# spider.net
KiCad netlist of a schematic drawn in EAGLE
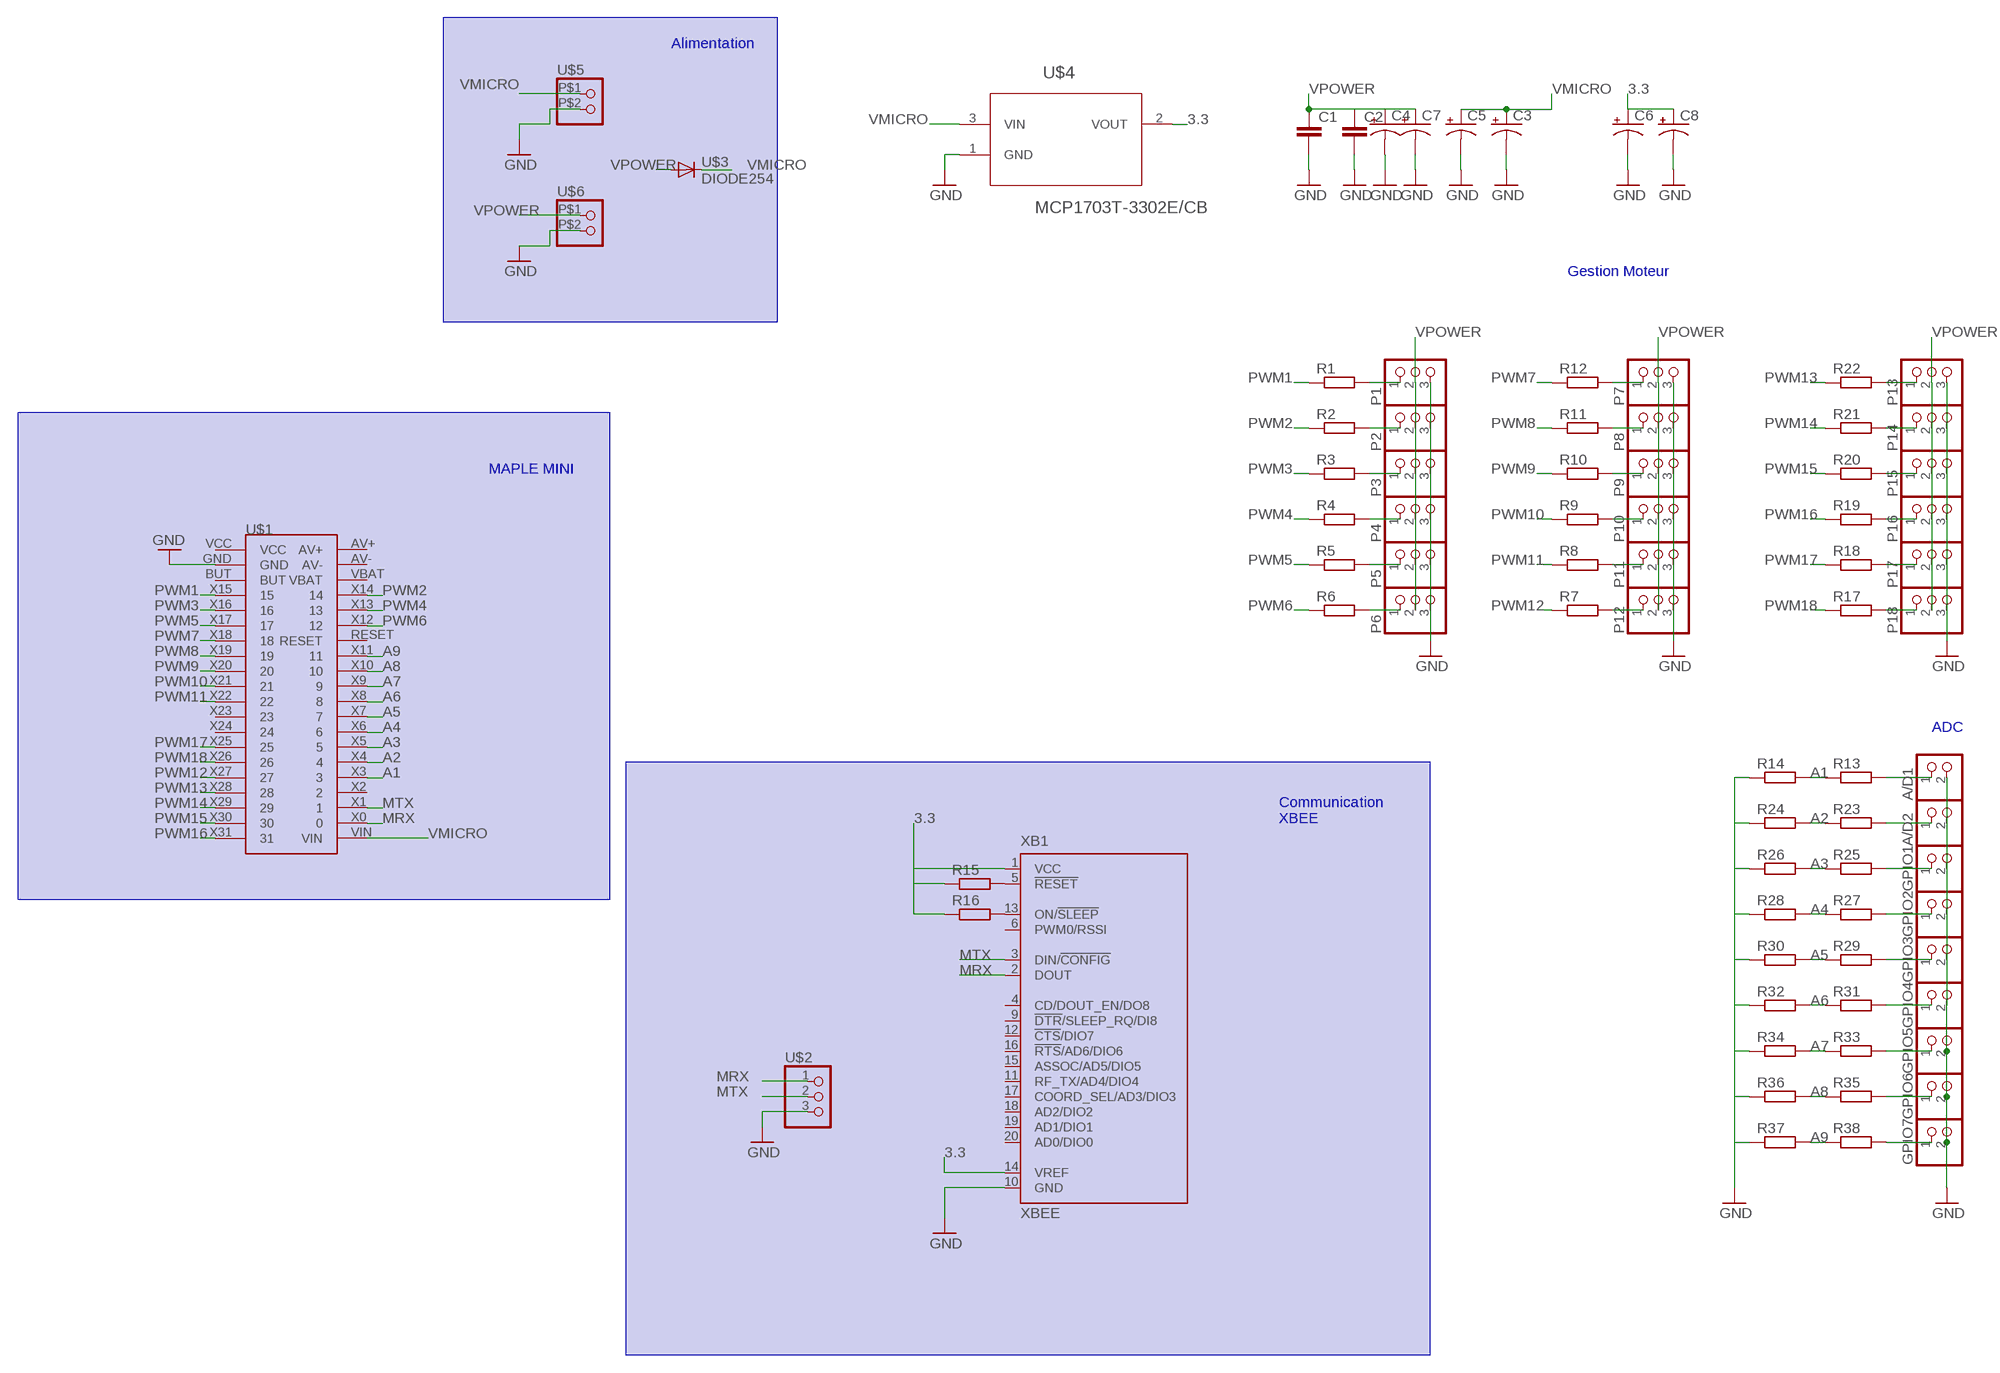
[diagram p0: schematic, sheet 1]

(export (version "E")
  (design (tool "Eeschema 10.0.6"))
  (components
    (comp (ref "A/D1")
      (value "CONNEC_1X02")
      (footprint "eagle-import:CONNEC_1X02")
      (libsource (lib "eagle-import") (part "rhoban_CONNEC_1X02"))
    )
    (comp (ref "A/D2")
      (value "CONNEC_1X02")
      (footprint "eagle-import:CONNEC_1X02")
      (libsource (lib "eagle-import") (part "rhoban_CONNEC_1X02"))
    )
    (comp (ref "C1")
      (value "C-EU075-032X103")
      (footprint "eagle-import:C075-032X103")
      (libsource (lib "eagle-import") (part "C-EU075-032X103"))
    )
    (comp (ref "C2")
      (value "C-EU075-032X103")
      (footprint "eagle-import:C075-032X103")
      (libsource (lib "eagle-import") (part "C-EU075-032X103"))
    )
    (comp (ref "C3")
      (value "CAP_POLPTH2")
      (footprint "eagle-import:CPOL-RADIAL-10UF-25V")
      (libsource (lib "eagle-import") (part "CAP_POLPTH2"))
    )
    (comp (ref "C4")
      (value "CAP_POLPTH2")
      (footprint "eagle-import:CPOL-RADIAL-10UF-25V")
      (libsource (lib "eagle-import") (part "CAP_POLPTH2"))
    )
    (comp (ref "C5")
      (value "CAP_POLPTH2")
      (footprint "eagle-import:CPOL-RADIAL-10UF-25V")
      (libsource (lib "eagle-import") (part "CAP_POLPTH2"))
    )
    (comp (ref "C6")
      (value "CAP_POLPTH2")
      (footprint "eagle-import:CPOL-RADIAL-10UF-25V")
      (libsource (lib "eagle-import") (part "CAP_POLPTH2"))
    )
    (comp (ref "C7")
      (value "CAP_POLPTH2")
      (footprint "eagle-import:CPOL-RADIAL-10UF-25V")
      (libsource (lib "eagle-import") (part "CAP_POLPTH2"))
    )
    (comp (ref "C8")
      (value "CAP_POLPTH2")
      (footprint "eagle-import:CPOL-RADIAL-10UF-25V")
      (libsource (lib "eagle-import") (part "CAP_POLPTH2"))
    )
    (comp (ref "GPIO1")
      (value "CONNEC_1X02")
      (footprint "eagle-import:CONNEC_1X02")
      (libsource (lib "eagle-import") (part "rhoban_CONNEC_1X02"))
    )
    (comp (ref "GPIO2")
      (value "CONNEC_1X02")
      (footprint "eagle-import:CONNEC_1X02")
      (libsource (lib "eagle-import") (part "rhoban_CONNEC_1X02"))
    )
    (comp (ref "GPIO3")
      (value "CONNEC_1X02")
      (footprint "eagle-import:CONNEC_1X02")
      (libsource (lib "eagle-import") (part "rhoban_CONNEC_1X02"))
    )
    (comp (ref "GPIO4")
      (value "CONNEC_1X02")
      (footprint "eagle-import:CONNEC_1X02")
      (libsource (lib "eagle-import") (part "rhoban_CONNEC_1X02"))
    )
    (comp (ref "GPIO5")
      (value "CONNEC_1X02")
      (footprint "eagle-import:CONNEC_1X02")
      (libsource (lib "eagle-import") (part "rhoban_CONNEC_1X02"))
    )
    (comp (ref "GPIO6")
      (value "CONNEC_1X02")
      (footprint "eagle-import:CONNEC_1X02")
      (libsource (lib "eagle-import") (part "rhoban_CONNEC_1X02"))
    )
    (comp (ref "GPIO7")
      (value "CONNEC_1X02")
      (footprint "eagle-import:CONNEC_1X02")
      (libsource (lib "eagle-import") (part "rhoban_CONNEC_1X02"))
    )
    (comp (ref "P1")
      (value "CONNEC_1X03")
      (footprint "eagle-import:CONNEC_1X03")
      (libsource (lib "eagle-import") (part "rhoban_CONNEC_1X03"))
    )
    (comp (ref "P2")
      (value "CONNEC_1X03")
      (footprint "eagle-import:CONNEC_1X03")
      (libsource (lib "eagle-import") (part "rhoban_CONNEC_1X03"))
    )
    (comp (ref "P3")
      (value "CONNEC_1X03")
      (footprint "eagle-import:CONNEC_1X03")
      (libsource (lib "eagle-import") (part "rhoban_CONNEC_1X03"))
    )
    (comp (ref "P4")
      (value "CONNEC_1X03")
      (footprint "eagle-import:CONNEC_1X03")
      (libsource (lib "eagle-import") (part "rhoban_CONNEC_1X03"))
    )
    (comp (ref "P5")
      (value "CONNEC_1X03")
      (footprint "eagle-import:CONNEC_1X03")
      (libsource (lib "eagle-import") (part "rhoban_CONNEC_1X03"))
    )
    (comp (ref "P6")
      (value "CONNEC_1X03")
      (footprint "eagle-import:CONNEC_1X03")
      (libsource (lib "eagle-import") (part "rhoban_CONNEC_1X03"))
    )
    (comp (ref "P7")
      (value "CONNEC_1X03")
      (footprint "eagle-import:CONNEC_1X03")
      (libsource (lib "eagle-import") (part "rhoban_CONNEC_1X03"))
    )
    (comp (ref "P8")
      (value "CONNEC_1X03")
      (footprint "eagle-import:CONNEC_1X03")
      (libsource (lib "eagle-import") (part "rhoban_CONNEC_1X03"))
    )
    (comp (ref "P9")
      (value "CONNEC_1X03")
      (footprint "eagle-import:CONNEC_1X03")
      (libsource (lib "eagle-import") (part "rhoban_CONNEC_1X03"))
    )
    (comp (ref "P10")
      (value "CONNEC_1X03")
      (footprint "eagle-import:CONNEC_1X03")
      (libsource (lib "eagle-import") (part "rhoban_CONNEC_1X03"))
    )
    (comp (ref "P11")
      (value "CONNEC_1X03")
      (footprint "eagle-import:CONNEC_1X03")
      (libsource (lib "eagle-import") (part "rhoban_CONNEC_1X03"))
    )
    (comp (ref "P12")
      (value "CONNEC_1X03")
      (footprint "eagle-import:CONNEC_1X03")
      (libsource (lib "eagle-import") (part "rhoban_CONNEC_1X03"))
    )
    (comp (ref "P13")
      (value "CONNEC_1X03")
      (footprint "eagle-import:CONNEC_1X03")
      (libsource (lib "eagle-import") (part "rhoban_CONNEC_1X03"))
    )
    (comp (ref "P14")
      (value "CONNEC_1X03")
      (footprint "eagle-import:CONNEC_1X03")
      (libsource (lib "eagle-import") (part "rhoban_CONNEC_1X03"))
    )
    (comp (ref "P15")
      (value "CONNEC_1X03")
      (footprint "eagle-import:CONNEC_1X03")
      (libsource (lib "eagle-import") (part "rhoban_CONNEC_1X03"))
    )
    (comp (ref "P16")
      (value "CONNEC_1X03")
      (footprint "eagle-import:CONNEC_1X03")
      (libsource (lib "eagle-import") (part "rhoban_CONNEC_1X03"))
    )
    (comp (ref "P17")
      (value "CONNEC_1X03")
      (footprint "eagle-import:CONNEC_1X03")
      (libsource (lib "eagle-import") (part "rhoban_CONNEC_1X03"))
    )
    (comp (ref "P18")
      (value "CONNEC_1X03")
      (footprint "eagle-import:CONNEC_1X03")
      (libsource (lib "eagle-import") (part "rhoban_CONNEC_1X03"))
    )
    (comp (ref "R1")
      (value "RESISTANCE-R0805")
      (footprint "eagle-import:R0805")
      (libsource (lib "eagle-import") (part "RESISTANCE-R0805"))
    )
    (comp (ref "R2")
      (value "RESISTANCE-R0805")
      (footprint "eagle-import:R0805")
      (libsource (lib "eagle-import") (part "RESISTANCE-R0805"))
    )
    (comp (ref "R3")
      (value "RESISTANCE-R0805")
      (footprint "eagle-import:R0805")
      (libsource (lib "eagle-import") (part "RESISTANCE-R0805"))
    )
    (comp (ref "R4")
      (value "RESISTANCE-R0805")
      (footprint "eagle-import:R0805")
      (libsource (lib "eagle-import") (part "RESISTANCE-R0805"))
    )
    (comp (ref "R5")
      (value "RESISTANCE-R0805")
      (footprint "eagle-import:R0805")
      (libsource (lib "eagle-import") (part "RESISTANCE-R0805"))
    )
    (comp (ref "R6")
      (value "RESISTANCE-R0805")
      (footprint "eagle-import:R0805")
      (libsource (lib "eagle-import") (part "RESISTANCE-R0805"))
    )
    (comp (ref "R7")
      (value "RESISTANCE-R0805")
      (footprint "eagle-import:R0805")
      (libsource (lib "eagle-import") (part "RESISTANCE-R0805"))
    )
    (comp (ref "R8")
      (value "RESISTANCE-R0805")
      (footprint "eagle-import:R0805")
      (libsource (lib "eagle-import") (part "RESISTANCE-R0805"))
    )
    (comp (ref "R9")
      (value "RESISTANCE-R0805")
      (footprint "eagle-import:R0805")
      (libsource (lib "eagle-import") (part "RESISTANCE-R0805"))
    )
    (comp (ref "R10")
      (value "RESISTANCE-R0805")
      (footprint "eagle-import:R0805")
      (libsource (lib "eagle-import") (part "RESISTANCE-R0805"))
    )
    (comp (ref "R11")
      (value "RESISTANCE-R0805")
      (footprint "eagle-import:R0805")
      (libsource (lib "eagle-import") (part "RESISTANCE-R0805"))
    )
    (comp (ref "R12")
      (value "RESISTANCE-R0805")
      (footprint "eagle-import:R0805")
      (libsource (lib "eagle-import") (part "RESISTANCE-R0805"))
    )
    (comp (ref "R13")
      (value "RESISTANCE-R0805")
      (footprint "eagle-import:R0805")
      (libsource (lib "eagle-import") (part "RESISTANCE-R0805"))
    )
    (comp (ref "R14")
      (value "RESISTANCE-R0805")
      (footprint "eagle-import:R0805")
      (libsource (lib "eagle-import") (part "RESISTANCE-R0805"))
    )
    (comp (ref "R15")
      (value "R-EU_R0805")
      (footprint "eagle-import:R0805")
      (libsource (lib "eagle-import") (part "R-EU_R0805"))
    )
    (comp (ref "R16")
      (value "R-EU_R0805")
      (footprint "eagle-import:R0805")
      (libsource (lib "eagle-import") (part "R-EU_R0805"))
    )
    (comp (ref "R17")
      (value "RESISTANCE-R0805")
      (footprint "eagle-import:R0805")
      (libsource (lib "eagle-import") (part "RESISTANCE-R0805"))
    )
    (comp (ref "R18")
      (value "RESISTANCE-R0805")
      (footprint "eagle-import:R0805")
      (libsource (lib "eagle-import") (part "RESISTANCE-R0805"))
    )
    (comp (ref "R19")
      (value "RESISTANCE-R0805")
      (footprint "eagle-import:R0805")
      (libsource (lib "eagle-import") (part "RESISTANCE-R0805"))
    )
    (comp (ref "R20")
      (value "RESISTANCE-R0805")
      (footprint "eagle-import:R0805")
      (libsource (lib "eagle-import") (part "RESISTANCE-R0805"))
    )
    (comp (ref "R21")
      (value "RESISTANCE-R0805")
      (footprint "eagle-import:R0805")
      (libsource (lib "eagle-import") (part "RESISTANCE-R0805"))
    )
    (comp (ref "R22")
      (value "RESISTANCE-R0805")
      (footprint "eagle-import:R0805")
      (libsource (lib "eagle-import") (part "RESISTANCE-R0805"))
    )
    (comp (ref "R23")
      (value "RESISTANCE-R0805")
      (footprint "eagle-import:R0805")
      (libsource (lib "eagle-import") (part "RESISTANCE-R0805"))
    )
    (comp (ref "R24")
      (value "RESISTANCE-R0805")
      (footprint "eagle-import:R0805")
      (libsource (lib "eagle-import") (part "RESISTANCE-R0805"))
    )
    (comp (ref "R25")
      (value "RESISTANCE-R0805")
      (footprint "eagle-import:R0805")
      (libsource (lib "eagle-import") (part "RESISTANCE-R0805"))
    )
    (comp (ref "R26")
      (value "RESISTANCE-R0805")
      (footprint "eagle-import:R0805")
      (libsource (lib "eagle-import") (part "RESISTANCE-R0805"))
    )
    (comp (ref "R27")
      (value "RESISTANCE-R0805")
      (footprint "eagle-import:R0805")
      (libsource (lib "eagle-import") (part "RESISTANCE-R0805"))
    )
    (comp (ref "R28")
      (value "RESISTANCE-R0805")
      (footprint "eagle-import:R0805")
      (libsource (lib "eagle-import") (part "RESISTANCE-R0805"))
    )
    (comp (ref "R29")
      (value "RESISTANCE-R0805")
      (footprint "eagle-import:R0805")
      (libsource (lib "eagle-import") (part "RESISTANCE-R0805"))
    )
    (comp (ref "R30")
      (value "RESISTANCE-R0805")
      (footprint "eagle-import:R0805")
      (libsource (lib "eagle-import") (part "RESISTANCE-R0805"))
    )
    (comp (ref "R31")
      (value "RESISTANCE-R0805")
      (footprint "eagle-import:R0805")
      (libsource (lib "eagle-import") (part "RESISTANCE-R0805"))
    )
    (comp (ref "R32")
      (value "RESISTANCE-R0805")
      (footprint "eagle-import:R0805")
      (libsource (lib "eagle-import") (part "RESISTANCE-R0805"))
    )
    (comp (ref "R33")
      (value "RESISTANCE-R0805")
      (footprint "eagle-import:R0805")
      (libsource (lib "eagle-import") (part "RESISTANCE-R0805"))
    )
    (comp (ref "R34")
      (value "RESISTANCE-R0805")
      (footprint "eagle-import:R0805")
      (libsource (lib "eagle-import") (part "RESISTANCE-R0805"))
    )
    (comp (ref "R35")
      (value "RESISTANCE-R0805")
      (footprint "eagle-import:R0805")
      (libsource (lib "eagle-import") (part "RESISTANCE-R0805"))
    )
    (comp (ref "R36")
      (value "RESISTANCE-R0805")
      (footprint "eagle-import:R0805")
      (libsource (lib "eagle-import") (part "RESISTANCE-R0805"))
    )
    (comp (ref "R37")
      (value "RESISTANCE-R0805")
      (footprint "eagle-import:R0805")
      (libsource (lib "eagle-import") (part "RESISTANCE-R0805"))
    )
    (comp (ref "R38")
      (value "RESISTANCE-R0805")
      (footprint "eagle-import:R0805")
      (libsource (lib "eagle-import") (part "RESISTANCE-R0805"))
    )
    (comp (ref "U$1")
      (value "MAPLE_MINI")
      (footprint "eagle-import:CONNEC_2X20")
      (libsource (lib "eagle-import") (part "MAPLE_MINI"))
    )
    (comp (ref "U$2")
      (value "CONNEC_1X03")
      (footprint "eagle-import:CONNEC_1X03")
      (libsource (lib "eagle-import") (part "CONNEC_1X03"))
    )
    (comp (ref "U$3")
      (value "DIODE254")
      (footprint "eagle-import:DIODE_254")
      (libsource (lib "eagle-import") (part "DIODE254"))
    )
    (comp (ref "U$4")
      (value "MCP1703T-3302E/CB")
      (footprint "eagle-import:SOT95P300X145-3N")
      (libsource (lib "eagle-import") (part "MCP1703T-3302E/CB"))
    )
    (comp (ref "U$5")
      (value "CONNEC_1X02BIG")
      (footprint "eagle-import:CONNEC_1X02_BIG")
      (libsource (lib "eagle-import") (part "CONNEC_1X02BIG"))
    )
    (comp (ref "U$6")
      (value "CONNEC_1X02BIG")
      (footprint "eagle-import:CONNEC_1X02_BIG")
      (libsource (lib "eagle-import") (part "CONNEC_1X02BIG"))
    )
    (comp (ref "XB1")
      (value "XBEE")
      (footprint "eagle-import:XBEE")
      (fields (field (name "MPN") "XBP24-Z7UIT-004"))
      (libsource (lib "eagle-import") (part "XBEE"))
    )
  )
  (nets
    (net (code "1") (name "/3.3") (class "Default")
      (node (ref "C6") (pin "1") (pinfunction "+_1") (pintype "passive"))
      (node (ref "C8") (pin "1") (pinfunction "+_1") (pintype "passive"))
      (node (ref "R15") (pin "1") (pinfunction "1_1") (pintype "passive"))
      (node (ref "R16") (pin "1") (pinfunction "1_1") (pintype "passive"))
      (node (ref "U$4") (pin "2") (pinfunction "VOUT_2") (pintype "output"))
      (node (ref "XB1") (pin "1") (pinfunction "VCC_1") (pintype "power_in"))
      (node (ref "XB1") (pin "14") (pinfunction "VREF_14") (pintype "input"))
    )
    (net (code "2") (name "/A1") (class "Default")
      (node (ref "R13") (pin "1") (pinfunction "1_1") (pintype "passive"))
      (node (ref "R14") (pin "2") (pinfunction "2_2") (pintype "passive"))
      (node (ref "U$1") (pin "X3") (pinfunction "3_X3") (pintype "bidirectional"))
    )
    (net (code "3") (name "/A2") (class "Default")
      (node (ref "R23") (pin "1") (pinfunction "1_1") (pintype "passive"))
      (node (ref "R24") (pin "2") (pinfunction "2_2") (pintype "passive"))
      (node (ref "U$1") (pin "X4") (pinfunction "4_X4") (pintype "bidirectional"))
    )
    (net (code "4") (name "/A3") (class "Default")
      (node (ref "R25") (pin "1") (pinfunction "1_1") (pintype "passive"))
      (node (ref "R26") (pin "2") (pinfunction "2_2") (pintype "passive"))
      (node (ref "U$1") (pin "X5") (pinfunction "5_X5") (pintype "bidirectional"))
    )
    (net (code "5") (name "/A4") (class "Default")
      (node (ref "R27") (pin "1") (pinfunction "1_1") (pintype "passive"))
      (node (ref "R28") (pin "2") (pinfunction "2_2") (pintype "passive"))
      (node (ref "U$1") (pin "X6") (pinfunction "6_X6") (pintype "bidirectional"))
    )
    (net (code "6") (name "/A5") (class "Default")
      (node (ref "R29") (pin "1") (pinfunction "1_1") (pintype "passive"))
      (node (ref "R30") (pin "2") (pinfunction "2_2") (pintype "passive"))
      (node (ref "U$1") (pin "X7") (pinfunction "7_X7") (pintype "bidirectional"))
    )
    (net (code "7") (name "/A6") (class "Default")
      (node (ref "R31") (pin "1") (pinfunction "1_1") (pintype "passive"))
      (node (ref "R32") (pin "2") (pinfunction "2_2") (pintype "passive"))
      (node (ref "U$1") (pin "X8") (pinfunction "8_X8") (pintype "bidirectional"))
    )
    (net (code "8") (name "/A7") (class "Default")
      (node (ref "R33") (pin "1") (pinfunction "1_1") (pintype "passive"))
      (node (ref "R34") (pin "2") (pinfunction "2_2") (pintype "passive"))
      (node (ref "U$1") (pin "X9") (pinfunction "9_X9") (pintype "bidirectional"))
    )
    (net (code "9") (name "/A8") (class "Default")
      (node (ref "R35") (pin "1") (pinfunction "1_1") (pintype "passive"))
      (node (ref "R36") (pin "2") (pinfunction "2_2") (pintype "passive"))
      (node (ref "U$1") (pin "X10") (pinfunction "10_X10") (pintype "bidirectional"))
    )
    (net (code "10") (name "/A9") (class "Default")
      (node (ref "R37") (pin "2") (pinfunction "2_2") (pintype "passive"))
      (node (ref "R38") (pin "1") (pinfunction "1_1") (pintype "passive"))
      (node (ref "U$1") (pin "X11") (pinfunction "11_X11") (pintype "bidirectional"))
    )
    (net (code "11") (name "/MRX") (class "Default")
      (node (ref "U$1") (pin "X0") (pinfunction "0_X0") (pintype "bidirectional"))
      (node (ref "U$2") (pin "1") (pinfunction "1_1") (pintype "passive"))
      (node (ref "XB1") (pin "2") (pinfunction "DOUT_2") (pintype "output"))
    )
    (net (code "12") (name "/MTX") (class "Default")
      (node (ref "U$1") (pin "X1") (pinfunction "1_X1") (pintype "bidirectional"))
      (node (ref "U$2") (pin "2") (pinfunction "2_2") (pintype "passive"))
      (node (ref "XB1") (pin "3") (pinfunction "DIN/~{CONFIG}_3") (pintype "input"))
    )
    (net (code "13") (name "/PWM1") (class "Default")
      (node (ref "R1") (pin "1") (pinfunction "1_1") (pintype "passive"))
      (node (ref "U$1") (pin "X15") (pinfunction "15_X15") (pintype "bidirectional"))
    )
    (net (code "14") (name "/PWM2") (class "Default")
      (node (ref "R2") (pin "1") (pinfunction "1_1") (pintype "passive"))
      (node (ref "U$1") (pin "X14") (pinfunction "14_X14") (pintype "bidirectional"))
    )
    (net (code "15") (name "/PWM3") (class "Default")
      (node (ref "R3") (pin "1") (pinfunction "1_1") (pintype "passive"))
      (node (ref "U$1") (pin "X16") (pinfunction "16_X16") (pintype "bidirectional"))
    )
    (net (code "16") (name "/PWM4") (class "Default")
      (node (ref "R4") (pin "1") (pinfunction "1_1") (pintype "passive"))
      (node (ref "U$1") (pin "X13") (pinfunction "13_X13") (pintype "bidirectional"))
    )
    (net (code "17") (name "/PWM5") (class "Default")
      (node (ref "R5") (pin "1") (pinfunction "1_1") (pintype "passive"))
      (node (ref "U$1") (pin "X17") (pinfunction "17_X17") (pintype "bidirectional"))
    )
    (net (code "18") (name "/PWM6") (class "Default")
      (node (ref "R6") (pin "1") (pinfunction "1_1") (pintype "passive"))
      (node (ref "U$1") (pin "X12") (pinfunction "12_X12") (pintype "bidirectional"))
    )
    (net (code "19") (name "/PWM7") (class "Default")
      (node (ref "R12") (pin "1") (pinfunction "1_1") (pintype "passive"))
      (node (ref "U$1") (pin "X18") (pinfunction "18_X18") (pintype "bidirectional"))
    )
    (net (code "20") (name "/PWM8") (class "Default")
      (node (ref "R11") (pin "1") (pinfunction "1_1") (pintype "passive"))
      (node (ref "U$1") (pin "X19") (pinfunction "19_X19") (pintype "bidirectional"))
    )
    (net (code "21") (name "/PWM9") (class "Default")
      (node (ref "R10") (pin "1") (pinfunction "1_1") (pintype "passive"))
      (node (ref "U$1") (pin "X20") (pinfunction "20_X20") (pintype "bidirectional"))
    )
    (net (code "22") (name "/PWM10") (class "Default")
      (node (ref "R9") (pin "1") (pinfunction "1_1") (pintype "passive"))
      (node (ref "U$1") (pin "X21") (pinfunction "21_X21") (pintype "bidirectional"))
    )
    (net (code "23") (name "/PWM11") (class "Default")
      (node (ref "R8") (pin "1") (pinfunction "1_1") (pintype "passive"))
      (node (ref "U$1") (pin "X22") (pinfunction "22_X22") (pintype "bidirectional"))
    )
    (net (code "24") (name "/PWM12") (class "Default")
      (node (ref "R7") (pin "1") (pinfunction "1_1") (pintype "passive"))
      (node (ref "U$1") (pin "X27") (pinfunction "27_X27") (pintype "bidirectional"))
    )
    (net (code "25") (name "/PWM13") (class "Default")
      (node (ref "R22") (pin "1") (pinfunction "1_1") (pintype "passive"))
      (node (ref "U$1") (pin "X28") (pinfunction "28_X28") (pintype "bidirectional"))
    )
    (net (code "26") (name "/PWM14") (class "Default")
      (node (ref "R21") (pin "1") (pinfunction "1_1") (pintype "passive"))
      (node (ref "U$1") (pin "X29") (pinfunction "29_X29") (pintype "bidirectional"))
    )
    (net (code "27") (name "/PWM15") (class "Default")
      (node (ref "R20") (pin "1") (pinfunction "1_1") (pintype "passive"))
      (node (ref "U$1") (pin "X30") (pinfunction "30_X30") (pintype "bidirectional"))
    )
    (net (code "28") (name "/PWM16") (class "Default")
      (node (ref "R19") (pin "1") (pinfunction "1_1") (pintype "passive"))
      (node (ref "U$1") (pin "X31") (pinfunction "31_X31") (pintype "bidirectional"))
    )
    (net (code "29") (name "/PWM17") (class "Default")
      (node (ref "R18") (pin "1") (pinfunction "1_1") (pintype "passive"))
      (node (ref "U$1") (pin "X25") (pinfunction "25_X25") (pintype "bidirectional"))
    )
    (net (code "30") (name "/PWM18") (class "Default")
      (node (ref "R17") (pin "1") (pinfunction "1_1") (pintype "passive"))
      (node (ref "U$1") (pin "X26") (pinfunction "26_X26") (pintype "bidirectional"))
    )
    (net (code "31") (name "/VMICRO") (class "Default")
      (node (ref "C3") (pin "1") (pinfunction "+_1") (pintype "passive"))
      (node (ref "C5") (pin "1") (pinfunction "+_1") (pintype "passive"))
      (node (ref "U$1") (pin "VIN") (pinfunction "VIN_VIN") (pintype "bidirectional"))
      (node (ref "U$3") (pin "B") (pinfunction "C_B") (pintype "passive"))
      (node (ref "U$4") (pin "3") (pinfunction "VIN_3") (pintype "input"))
      (node (ref "U$5") (pin "P$1") (pinfunction "1_P$1") (pintype "passive"))
    )
    (net (code "32") (name "/VPOWER") (class "Default")
      (node (ref "C1") (pin "1") (pinfunction "1_1") (pintype "passive"))
      (node (ref "C2") (pin "1") (pinfunction "1_1") (pintype "passive"))
      (node (ref "C4") (pin "1") (pinfunction "+_1") (pintype "passive"))
      (node (ref "C7") (pin "1") (pinfunction "+_1") (pintype "passive"))
      (node (ref "P1") (pin "2") (pinfunction "2_2") (pintype "passive"))
      (node (ref "P10") (pin "2") (pinfunction "2_2") (pintype "passive"))
      (node (ref "P11") (pin "2") (pinfunction "2_2") (pintype "passive"))
      (node (ref "P12") (pin "2") (pinfunction "2_2") (pintype "passive"))
      (node (ref "P13") (pin "2") (pinfunction "2_2") (pintype "passive"))
      (node (ref "P14") (pin "2") (pinfunction "2_2") (pintype "passive"))
      (node (ref "P15") (pin "2") (pinfunction "2_2") (pintype "passive"))
      (node (ref "P16") (pin "2") (pinfunction "2_2") (pintype "passive"))
      (node (ref "P17") (pin "2") (pinfunction "2_2") (pintype "passive"))
      (node (ref "P18") (pin "2") (pinfunction "2_2") (pintype "passive"))
      (node (ref "P2") (pin "2") (pinfunction "2_2") (pintype "passive"))
      (node (ref "P3") (pin "2") (pinfunction "2_2") (pintype "passive"))
      (node (ref "P4") (pin "2") (pinfunction "2_2") (pintype "passive"))
      (node (ref "P5") (pin "2") (pinfunction "2_2") (pintype "passive"))
      (node (ref "P6") (pin "2") (pinfunction "2_2") (pintype "passive"))
      (node (ref "P7") (pin "2") (pinfunction "2_2") (pintype "passive"))
      (node (ref "P8") (pin "2") (pinfunction "2_2") (pintype "passive"))
      (node (ref "P9") (pin "2") (pinfunction "2_2") (pintype "passive"))
      (node (ref "U$3") (pin "A") (pinfunction "A_A") (pintype "passive"))
      (node (ref "U$6") (pin "P$1") (pinfunction "1_P$1") (pintype "passive"))
    )
    (net (code "33") (name "GND") (class "Default")
      (node (ref "A/D1") (pin "2") (pinfunction "2_2") (pintype "passive"))
      (node (ref "A/D2") (pin "2") (pinfunction "2_2") (pintype "passive"))
      (node (ref "C1") (pin "2") (pinfunction "2_2") (pintype "passive"))
      (node (ref "C2") (pin "2") (pinfunction "2_2") (pintype "passive"))
      (node (ref "C3") (pin "2") (pinfunction "-_2") (pintype "passive"))
      (node (ref "C4") (pin "2") (pinfunction "-_2") (pintype "passive"))
      (node (ref "C5") (pin "2") (pinfunction "-_2") (pintype "passive"))
      (node (ref "C6") (pin "2") (pinfunction "-_2") (pintype "passive"))
      (node (ref "C7") (pin "2") (pinfunction "-_2") (pintype "passive"))
      (node (ref "C8") (pin "2") (pinfunction "-_2") (pintype "passive"))
      (node (ref "GPIO1") (pin "2") (pinfunction "2_2") (pintype "passive"))
      (node (ref "GPIO2") (pin "2") (pinfunction "2_2") (pintype "passive"))
      (node (ref "GPIO3") (pin "2") (pinfunction "2_2") (pintype "passive"))
      (node (ref "GPIO4") (pin "2") (pinfunction "2_2") (pintype "passive"))
      (node (ref "GPIO5") (pin "2") (pinfunction "2_2") (pintype "passive"))
      (node (ref "GPIO6") (pin "2") (pinfunction "2_2") (pintype "passive"))
      (node (ref "GPIO7") (pin "2") (pinfunction "2_2") (pintype "passive"))
      (node (ref "P1") (pin "3") (pinfunction "3_3") (pintype "passive"))
      (node (ref "P10") (pin "3") (pinfunction "3_3") (pintype "passive"))
      (node (ref "P11") (pin "3") (pinfunction "3_3") (pintype "passive"))
      (node (ref "P12") (pin "3") (pinfunction "3_3") (pintype "passive"))
      (node (ref "P13") (pin "3") (pinfunction "3_3") (pintype "passive"))
      (node (ref "P14") (pin "3") (pinfunction "3_3") (pintype "passive"))
      (node (ref "P15") (pin "3") (pinfunction "3_3") (pintype "passive"))
      (node (ref "P16") (pin "3") (pinfunction "3_3") (pintype "passive"))
      (node (ref "P17") (pin "3") (pinfunction "3_3") (pintype "passive"))
      (node (ref "P18") (pin "3") (pinfunction "3_3") (pintype "passive"))
      (node (ref "P2") (pin "3") (pinfunction "3_3") (pintype "passive"))
      (node (ref "P3") (pin "3") (pinfunction "3_3") (pintype "passive"))
      (node (ref "P4") (pin "3") (pinfunction "3_3") (pintype "passive"))
      (node (ref "P5") (pin "3") (pinfunction "3_3") (pintype "passive"))
      (node (ref "P6") (pin "3") (pinfunction "3_3") (pintype "passive"))
      (node (ref "P7") (pin "3") (pinfunction "3_3") (pintype "passive"))
      (node (ref "P8") (pin "3") (pinfunction "3_3") (pintype "passive"))
      (node (ref "P9") (pin "3") (pinfunction "3_3") (pintype "passive"))
      (node (ref "R14") (pin "1") (pinfunction "1_1") (pintype "passive"))
      (node (ref "R24") (pin "1") (pinfunction "1_1") (pintype "passive"))
      (node (ref "R26") (pin "1") (pinfunction "1_1") (pintype "passive"))
      (node (ref "R28") (pin "1") (pinfunction "1_1") (pintype "passive"))
      (node (ref "R30") (pin "1") (pinfunction "1_1") (pintype "passive"))
      (node (ref "R32") (pin "1") (pinfunction "1_1") (pintype "passive"))
      (node (ref "R34") (pin "1") (pinfunction "1_1") (pintype "passive"))
      (node (ref "R36") (pin "1") (pinfunction "1_1") (pintype "passive"))
      (node (ref "R37") (pin "1") (pinfunction "1_1") (pintype "passive"))
      (node (ref "U$1") (pin "GND") (pinfunction "GND_GND") (pintype "bidirectional"))
      (node (ref "U$2") (pin "3") (pinfunction "3_3") (pintype "passive"))
      (node (ref "U$4") (pin "1") (pinfunction "GND_1") (pintype "passive"))
      (node (ref "U$5") (pin "P$2") (pinfunction "2_P$2") (pintype "passive"))
      (node (ref "U$6") (pin "P$2") (pinfunction "2_P$2") (pintype "passive"))
      (node (ref "XB1") (pin "10") (pinfunction "GND_10") (pintype "power_in"))
    )
    (net (code "34") (name "Net-(A/D1-Pad1)") (class "Default")
      (node (ref "A/D1") (pin "1") (pinfunction "1_1") (pintype "passive"))
      (node (ref "R13") (pin "2") (pinfunction "2_2") (pintype "passive"))
    )
    (net (code "35") (name "Net-(A/D2-Pad1)") (class "Default")
      (node (ref "A/D2") (pin "1") (pinfunction "1_1") (pintype "passive"))
      (node (ref "R23") (pin "2") (pinfunction "2_2") (pintype "passive"))
    )
    (net (code "36") (name "Net-(GPIO1-Pad1)") (class "Default")
      (node (ref "GPIO1") (pin "1") (pinfunction "1_1") (pintype "passive"))
      (node (ref "R25") (pin "2") (pinfunction "2_2") (pintype "passive"))
    )
    (net (code "37") (name "Net-(GPIO2-Pad1)") (class "Default")
      (node (ref "GPIO2") (pin "1") (pinfunction "1_1") (pintype "passive"))
      (node (ref "R27") (pin "2") (pinfunction "2_2") (pintype "passive"))
    )
    (net (code "38") (name "Net-(GPIO3-Pad1)") (class "Default")
      (node (ref "GPIO3") (pin "1") (pinfunction "1_1") (pintype "passive"))
      (node (ref "R29") (pin "2") (pinfunction "2_2") (pintype "passive"))
    )
    (net (code "39") (name "Net-(GPIO4-Pad1)") (class "Default")
      (node (ref "GPIO4") (pin "1") (pinfunction "1_1") (pintype "passive"))
      (node (ref "R31") (pin "2") (pinfunction "2_2") (pintype "passive"))
    )
    (net (code "40") (name "Net-(GPIO5-Pad1)") (class "Default")
      (node (ref "GPIO5") (pin "1") (pinfunction "1_1") (pintype "passive"))
      (node (ref "R33") (pin "2") (pinfunction "2_2") (pintype "passive"))
    )
    (net (code "41") (name "Net-(GPIO6-Pad1)") (class "Default")
      (node (ref "GPIO6") (pin "1") (pinfunction "1_1") (pintype "passive"))
      (node (ref "R35") (pin "2") (pinfunction "2_2") (pintype "passive"))
    )
    (net (code "42") (name "Net-(GPIO7-Pad1)") (class "Default")
      (node (ref "GPIO7") (pin "1") (pinfunction "1_1") (pintype "passive"))
      (node (ref "R38") (pin "2") (pinfunction "2_2") (pintype "passive"))
    )
    (net (code "43") (name "Net-(P1-Pad1)") (class "Default")
      (node (ref "P1") (pin "1") (pinfunction "1_1") (pintype "passive"))
      (node (ref "R1") (pin "2") (pinfunction "2_2") (pintype "passive"))
    )
    (net (code "44") (name "Net-(P2-Pad1)") (class "Default")
      (node (ref "P2") (pin "1") (pinfunction "1_1") (pintype "passive"))
      (node (ref "R2") (pin "2") (pinfunction "2_2") (pintype "passive"))
    )
    (net (code "45") (name "Net-(P3-Pad1)") (class "Default")
      (node (ref "P3") (pin "1") (pinfunction "1_1") (pintype "passive"))
      (node (ref "R3") (pin "2") (pinfunction "2_2") (pintype "passive"))
    )
    (net (code "46") (name "Net-(P4-Pad1)") (class "Default")
      (node (ref "P4") (pin "1") (pinfunction "1_1") (pintype "passive"))
      (node (ref "R4") (pin "2") (pinfunction "2_2") (pintype "passive"))
    )
    (net (code "47") (name "Net-(P5-Pad1)") (class "Default")
      (node (ref "P5") (pin "1") (pinfunction "1_1") (pintype "passive"))
      (node (ref "R5") (pin "2") (pinfunction "2_2") (pintype "passive"))
    )
    (net (code "48") (name "Net-(P6-Pad1)") (class "Default")
      (node (ref "P6") (pin "1") (pinfunction "1_1") (pintype "passive"))
      (node (ref "R6") (pin "2") (pinfunction "2_2") (pintype "passive"))
    )
    (net (code "49") (name "Net-(P7-Pad1)") (class "Default")
      (node (ref "P7") (pin "1") (pinfunction "1_1") (pintype "passive"))
      (node (ref "R12") (pin "2") (pinfunction "2_2") (pintype "passive"))
    )
    (net (code "50") (name "Net-(P8-Pad1)") (class "Default")
      (node (ref "P8") (pin "1") (pinfunction "1_1") (pintype "passive"))
      (node (ref "R11") (pin "2") (pinfunction "2_2") (pintype "passive"))
    )
    (net (code "51") (name "Net-(P9-Pad1)") (class "Default")
      (node (ref "P9") (pin "1") (pinfunction "1_1") (pintype "passive"))
      (node (ref "R10") (pin "2") (pinfunction "2_2") (pintype "passive"))
    )
    (net (code "52") (name "Net-(P10-Pad1)") (class "Default")
      (node (ref "P10") (pin "1") (pinfunction "1_1") (pintype "passive"))
      (node (ref "R9") (pin "2") (pinfunction "2_2") (pintype "passive"))
    )
    (net (code "53") (name "Net-(P11-Pad1)") (class "Default")
      (node (ref "P11") (pin "1") (pinfunction "1_1") (pintype "passive"))
      (node (ref "R8") (pin "2") (pinfunction "2_2") (pintype "passive"))
    )
    (net (code "54") (name "Net-(P12-Pad1)") (class "Default")
      (node (ref "P12") (pin "1") (pinfunction "1_1") (pintype "passive"))
      (node (ref "R7") (pin "2") (pinfunction "2_2") (pintype "passive"))
    )
    (net (code "55") (name "Net-(P13-Pad1)") (class "Default")
      (node (ref "P13") (pin "1") (pinfunction "1_1") (pintype "passive"))
      (node (ref "R22") (pin "2") (pinfunction "2_2") (pintype "passive"))
    )
    (net (code "56") (name "Net-(P14-Pad1)") (class "Default")
      (node (ref "P14") (pin "1") (pinfunction "1_1") (pintype "passive"))
      (node (ref "R21") (pin "2") (pinfunction "2_2") (pintype "passive"))
    )
    (net (code "57") (name "Net-(P15-Pad1)") (class "Default")
      (node (ref "P15") (pin "1") (pinfunction "1_1") (pintype "passive"))
      (node (ref "R20") (pin "2") (pinfunction "2_2") (pintype "passive"))
    )
    (net (code "58") (name "Net-(P16-Pad1)") (class "Default")
      (node (ref "P16") (pin "1") (pinfunction "1_1") (pintype "passive"))
      (node (ref "R19") (pin "2") (pinfunction "2_2") (pintype "passive"))
    )
    (net (code "59") (name "Net-(P17-Pad1)") (class "Default")
      (node (ref "P17") (pin "1") (pinfunction "1_1") (pintype "passive"))
      (node (ref "R18") (pin "2") (pinfunction "2_2") (pintype "passive"))
    )
    (net (code "60") (name "Net-(P18-Pad1)") (class "Default")
      (node (ref "P18") (pin "1") (pinfunction "1_1") (pintype "passive"))
      (node (ref "R17") (pin "2") (pinfunction "2_2") (pintype "passive"))
    )
    (net (code "61") (name "Net-(XB1-ON{slash}~{SLEEP})") (class "Default")
      (node (ref "R16") (pin "2") (pinfunction "2_2") (pintype "passive"))
      (node (ref "XB1") (pin "13") (pinfunction "ON/~{SLEEP}_13") (pintype "output"))
    )
    (net (code "62") (name "Net-(XB1-~{RESET})") (class "Default")
      (node (ref "R15") (pin "2") (pinfunction "2_2") (pintype "passive"))
      (node (ref "XB1") (pin "5") (pinfunction "~{RESET}_5") (pintype "input"))
    )
    (net (code "63") (name "unconnected-(U$1-2-PadX2)") (class "Default")
      (node (ref "U$1") (pin "X2") (pinfunction "2_X2") (pintype "bidirectional"))
    )
    (net (code "64") (name "unconnected-(U$1-23-PadX23)") (class "Default")
      (node (ref "U$1") (pin "X23") (pinfunction "23_X23") (pintype "bidirectional"))
    )
    (net (code "65") (name "unconnected-(U$1-24-PadX24)") (class "Default")
      (node (ref "U$1") (pin "X24") (pinfunction "24_X24") (pintype "bidirectional"))
    )
    (net (code "66") (name "unconnected-(U$1-PadAV+)") (class "Default")
      (node (ref "U$1") (pin "AV+") (pinfunction "AV+_AV+") (pintype "bidirectional"))
    )
    (net (code "67") (name "unconnected-(U$1-PadAV-)") (class "Default")
      (node (ref "U$1") (pin "AV-") (pinfunction "AV-_AV-") (pintype "bidirectional"))
    )
    (net (code "68") (name "unconnected-(U$1-PadBUT)") (class "Default")
      (node (ref "U$1") (pin "BUT") (pinfunction "BUT_BUT") (pintype "bidirectional"))
    )
    (net (code "69") (name "unconnected-(U$1-PadRESET)") (class "Default")
      (node (ref "U$1") (pin "RESET") (pinfunction "RESET_RESET") (pintype "bidirectional"))
    )
    (net (code "70") (name "unconnected-(U$1-PadVBAT)") (class "Default")
      (node (ref "U$1") (pin "VBAT") (pinfunction "VBAT_VBAT") (pintype "bidirectional"))
    )
    (net (code "71") (name "unconnected-(U$1-PadVCC)") (class "Default")
      (node (ref "U$1") (pin "VCC") (pinfunction "VCC_VCC") (pintype "bidirectional"))
    )
    (net (code "72") (name "unconnected-(XB1-AD0{slash}DIO0-Pad20)") (class "Default")
      (node (ref "XB1") (pin "20") (pinfunction "AD0/DIO0_20") (pintype "bidirectional"))
    )
    (net (code "73") (name "unconnected-(XB1-AD1{slash}DIO1-Pad19)") (class "Default")
      (node (ref "XB1") (pin "19") (pinfunction "AD1/DIO1_19") (pintype "bidirectional"))
    )
    (net (code "74") (name "unconnected-(XB1-AD2{slash}DIO2-Pad18)") (class "Default")
      (node (ref "XB1") (pin "18") (pinfunction "AD2/DIO2_18") (pintype "bidirectional"))
    )
    (net (code "75") (name "unconnected-(XB1-ASSOC{slash}AD5{slash}DIO5-Pad15)") (class "Default")
      (node (ref "XB1") (pin "15") (pinfunction "ASSOC/AD5/DIO5_15") (pintype "bidirectional"))
    )
    (net (code "76") (name "unconnected-(XB1-CD{slash}DOUT_EN{slash}DO8-Pad4)") (class "Default")
      (node (ref "XB1") (pin "4") (pinfunction "CD/DOUT_EN/DO8_4") (pintype "output"))
    )
    (net (code "77") (name "unconnected-(XB1-COORD_SEL{slash}AD3{slash}DIO3-Pad17)") (class "Default")
      (node (ref "XB1") (pin "17") (pinfunction "COORD_SEL/AD3/DIO3_17") (pintype "bidirectional"))
    )
    (net (code "78") (name "unconnected-(XB1-PWM0{slash}RSSI-Pad6)") (class "Default")
      (node (ref "XB1") (pin "6") (pinfunction "PWM0/RSSI_6") (pintype "output"))
    )
    (net (code "79") (name "unconnected-(XB1-RF_TX{slash}AD4{slash}DIO4-Pad11)") (class "Default")
      (node (ref "XB1") (pin "11") (pinfunction "RF_TX/AD4/DIO4_11") (pintype "bidirectional"))
    )
    (net (code "80") (name "unconnected-(XB1-~{CTS}{slash}DIO7-Pad12)") (class "Default")
      (node (ref "XB1") (pin "12") (pinfunction "~{CTS}/DIO7_12") (pintype "bidirectional"))
    )
    (net (code "81") (name "unconnected-(XB1-~{DTR}{slash}SLEEP_RQ{slash}DI8-Pad9)") (class "Default")
      (node (ref "XB1") (pin "9") (pinfunction "~{DTR}/SLEEP_RQ/DI8_9") (pintype "bidirectional"))
    )
    (net (code "82") (name "unconnected-(XB1-~{RTS}{slash}AD6{slash}DIO6-Pad16)") (class "Default")
      (node (ref "XB1") (pin "16") (pinfunction "~{RTS}/AD6/DIO6_16") (pintype "bidirectional"))
    )
  )
)
